# PCB_Draft_4.net
KiCad netlist of a schematic drawn in EAGLE
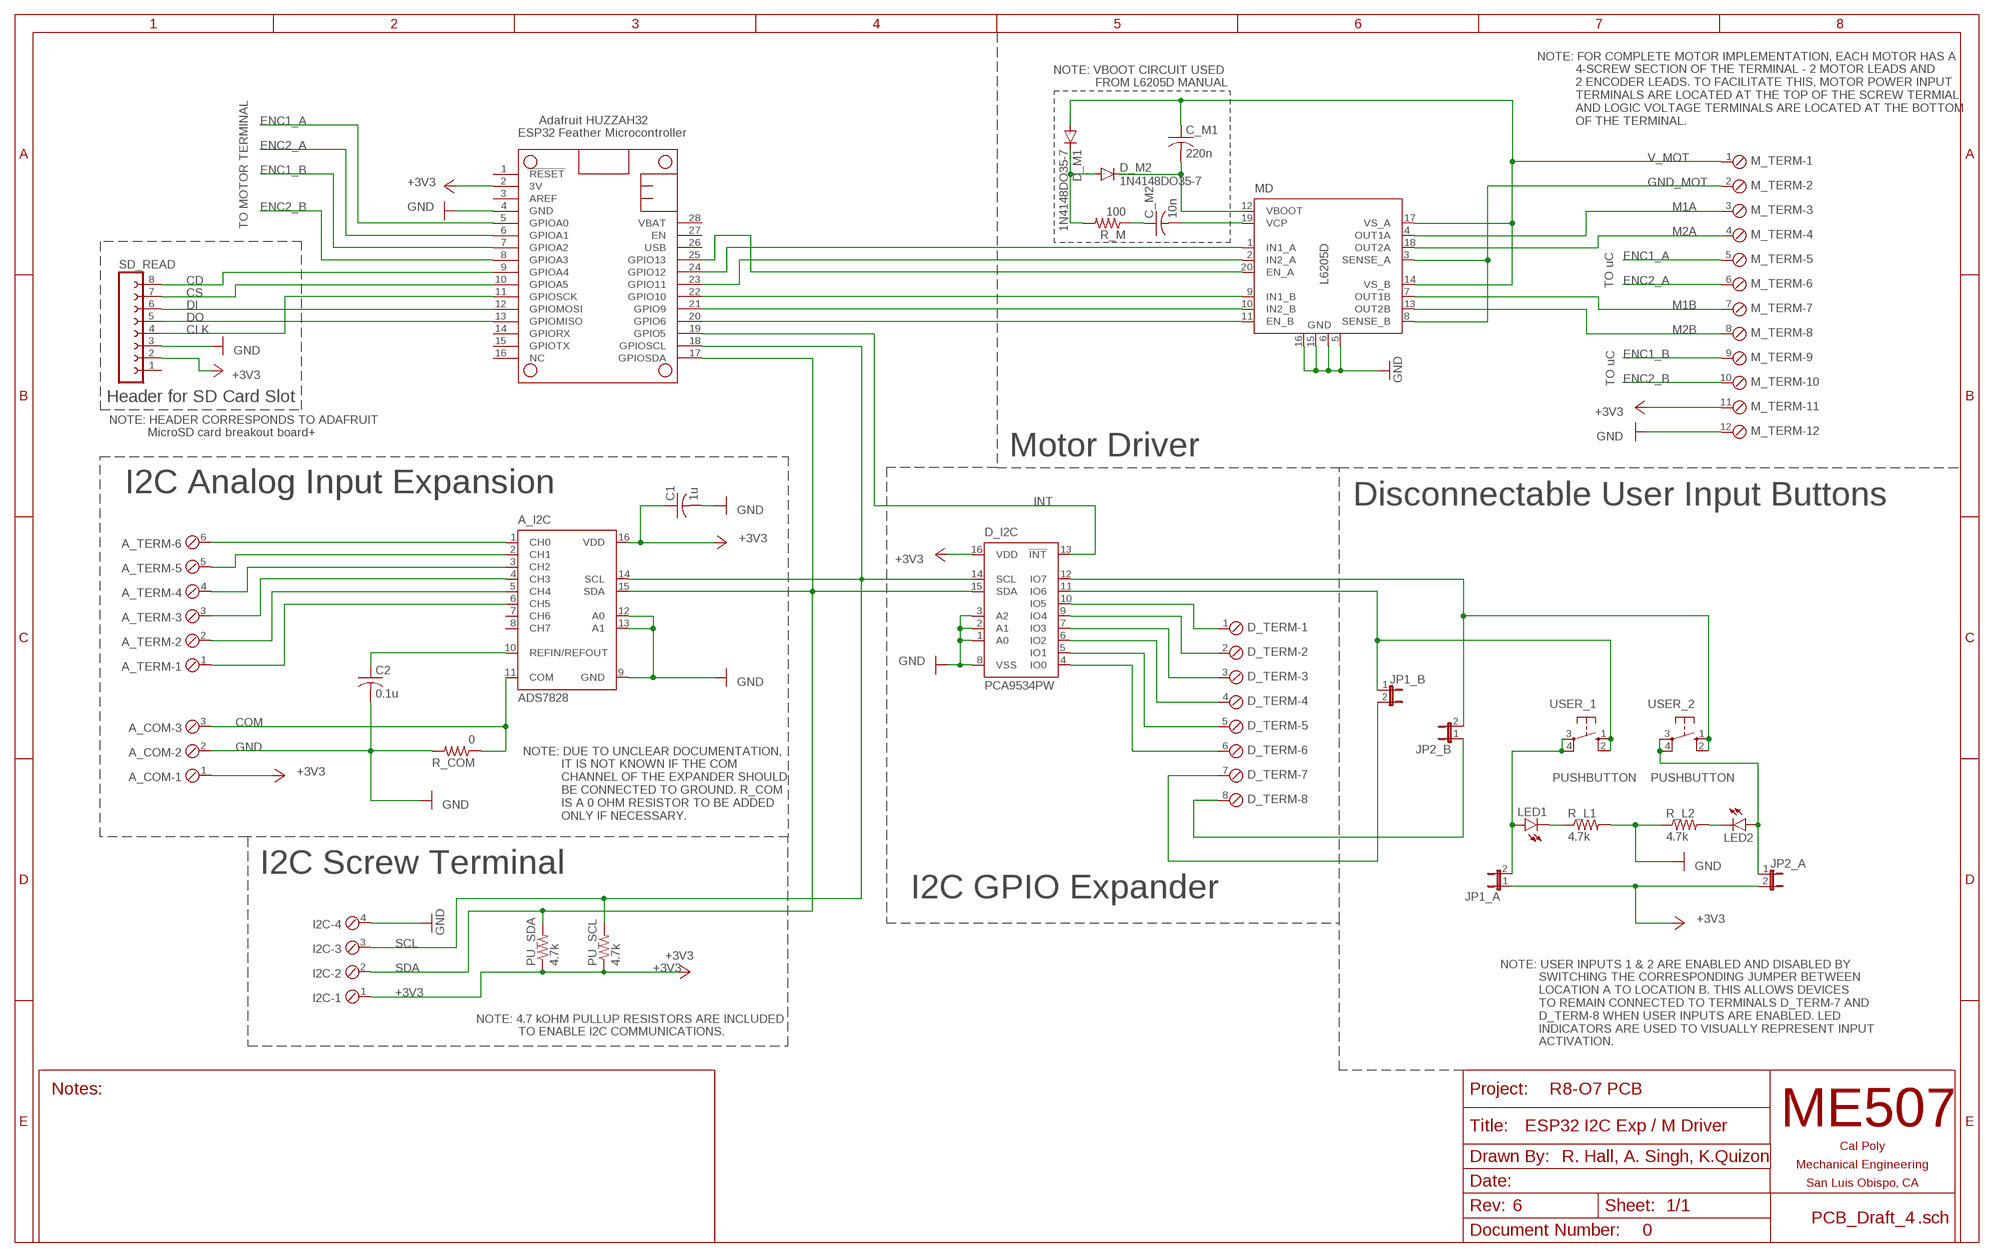
[diagram p0: schematic, sheet 1]

(export (version "E")
  (design (tool "Eeschema 10.0.6"))
  (components
    (comp (ref "A_COM")
      (value "SCREWTERM_3P_254")
      (footprint "eagle-import:3POL254")
      (libsource (lib "eagle-import") (part "SCREWTERM_3P_254"))
    )
    (comp (ref "A_I2C")
      (value "ADS7828")
      (footprint "eagle-import:TSSOP16-PW")
      (fields (field (name "MF") "TEXAS INSTRUMENTS") (field (name "MPN") "ADS7828E/250"))
      (libsource (lib "eagle-import") (part "ADS7828"))
    )
    (comp (ref "A_TERM")
      (value "SCREWTERM_6P_254")
      (footprint "eagle-import:6POL254")
      (libsource (lib "eagle-import") (part "SCREWTERM_6P_254"))
    )
    (comp (ref "C1")
      (value "1u")
      (footprint "eagle-import:C0805")
      (libsource (lib "eagle-import") (part "C-USC0805"))
    )
    (comp (ref "C2")
      (value "0.1u")
      (footprint "eagle-import:C0805")
      (libsource (lib "eagle-import") (part "C-USC0805"))
    )
    (comp (ref "C_M1")
      (value "220n")
      (footprint "eagle-import:C0805")
      (libsource (lib "eagle-import") (part "C-USC0805"))
    )
    (comp (ref "C_M2")
      (value "10n")
      (footprint "eagle-import:C0805")
      (libsource (lib "eagle-import") (part "C-USC0805"))
    )
    (comp (ref "D_I2C")
      (value "PCA9534PW")
      (footprint "eagle-import:TSSOP16")
      (libsource (lib "eagle-import") (part "PCA9534PW"))
    )
    (comp (ref "D_M1")
      (value "1N4148DO35-7")
      (footprint "eagle-import:DO35-7")
      (libsource (lib "eagle-import") (part "1N4148DO35-7"))
    )
    (comp (ref "D_M2")
      (value "1N4148DO35-7")
      (footprint "eagle-import:DO35-7")
      (libsource (lib "eagle-import") (part "1N4148DO35-7"))
    )
    (comp (ref "D_TERM")
      (value "SCREWTERM_8P_254")
      (footprint "eagle-import:8POL254")
      (libsource (lib "eagle-import") (part "SCREWTERM_8P_254"))
    )
    (comp (ref "FTHRWNG")
      (value "FEATHERWINGEXTENDED_BOTH_ENDS")
      (footprint "eagle-import:FEATHERWING")
      (libsource (lib "eagle-import") (part "FEATHERWINGEXTENDED_BOTH_ENDS"))
    )
    (comp (ref "I2C")
      (value "SCREWTERM_4P_254")
      (footprint "eagle-import:4POL254")
      (libsource (lib "eagle-import") (part "SCREWTERM_4P_254"))
    )
    (comp (ref "JP1_A")
      (value "JP1E")
      (footprint "eagle-import:JP1")
      (libsource (lib "eagle-import") (part "JP1E"))
    )
    (comp (ref "JP1_B")
      (value "JP1E")
      (footprint "eagle-import:JP1")
      (libsource (lib "eagle-import") (part "JP1E"))
    )
    (comp (ref "JP2_A")
      (value "JP1E")
      (footprint "eagle-import:JP1")
      (libsource (lib "eagle-import") (part "JP1E"))
    )
    (comp (ref "JP2_B")
      (value "JP1E")
      (footprint "eagle-import:JP1")
      (libsource (lib "eagle-import") (part "JP1E"))
    )
    (comp (ref "LED1")
      (value "LEDCHIP-LED0805")
      (footprint "eagle-import:CHIP-LED0805")
      (libsource (lib "eagle-import") (part "LEDCHIP-LED0805"))
    )
    (comp (ref "LED2")
      (value "LEDCHIP-LED0805")
      (footprint "eagle-import:CHIP-LED0805")
      (libsource (lib "eagle-import") (part "LEDCHIP-LED0805"))
    )
    (comp (ref "MD")
      (value "L6205D")
      (footprint "eagle-import:SO20")
      (libsource (lib "eagle-import") (part "L6205D"))
    )
    (comp (ref "M_TERM")
      (value "SCREWTERM_12P_254")
      (footprint "eagle-import:12POL254")
      (libsource (lib "eagle-import") (part "SCREWTERM_12P_254"))
    )
    (comp (ref "PU_SCL")
      (value "4.7k")
      (footprint "eagle-import:M0805")
      (libsource (lib "eagle-import") (part "R-US_M0805"))
    )
    (comp (ref "PU_SDA")
      (value "4.7k")
      (footprint "eagle-import:M0805")
      (libsource (lib "eagle-import") (part "R-US_M0805"))
    )
    (comp (ref "R_COM")
      (value "0")
      (footprint "eagle-import:M0805")
      (libsource (lib "eagle-import") (part "R-US_M0805"))
    )
    (comp (ref "R_L1")
      (value "4.7k")
      (footprint "eagle-import:M0805")
      (libsource (lib "eagle-import") (part "R-US_M0805"))
    )
    (comp (ref "R_L2")
      (value "4.7k")
      (footprint "eagle-import:M0805")
      (libsource (lib "eagle-import") (part "R-US_M0805"))
    )
    (comp (ref "R_M")
      (value "100")
      (footprint "eagle-import:M0805")
      (libsource (lib "eagle-import") (part "R-US_M0805"))
    )
    (comp (ref "SD_READ")
      (value "FE08-1")
      (footprint "eagle-import:FE08")
      (libsource (lib "eagle-import") (part "FE08-1"))
    )
    (comp (ref "USER_1")
      (value "PUSHBUTTON")
      (footprint "eagle-import:B3F-10XX")
      (fields (field (name "MPN") "B3F-1000"))
      (libsource (lib "eagle-import") (part "PUSHBUTTON"))
    )
    (comp (ref "USER_2")
      (value "PUSHBUTTON")
      (footprint "eagle-import:B3F-10XX")
      (fields (field (name "MPN") "B3F-1000"))
      (libsource (lib "eagle-import") (part "PUSHBUTTON"))
    )
  )
  (nets
    (net (code "1") (name "+3V3") (class "Default")
      (node (ref "A_COM") (pin "1") (pinfunction "1_1") (pintype "passive"))
      (node (ref "A_I2C") (pin "16") (pinfunction "VDD_16") (pintype "power_in"))
      (node (ref "C1") (pin "1") (pinfunction "1_1") (pintype "passive"))
      (node (ref "D_I2C") (pin "16") (pinfunction "VDD_16") (pintype "power_in"))
      (node (ref "FTHRWNG") (pin "2") (pinfunction "3V_2") (pintype "power_in"))
      (node (ref "I2C") (pin "1") (pinfunction "1_1") (pintype "passive"))
      (node (ref "JP1_A") (pin "1") (pinfunction "1_1") (pintype "passive"))
      (node (ref "JP2_A") (pin "2") (pinfunction "2_2") (pintype "passive"))
      (node (ref "M_TERM") (pin "11") (pinfunction "1_11") (pintype "passive"))
      (node (ref "PU_SCL") (pin "1") (pinfunction "1_1") (pintype "passive"))
      (node (ref "PU_SDA") (pin "1") (pinfunction "1_1") (pintype "passive"))
      (node (ref "SD_READ") (pin "2") (pinfunction "2_2") (pintype "passive"))
    )
    (net (code "2") (name "/CD") (class "Default")
      (node (ref "FTHRWNG") (pin "9") (pinfunction "GPIOA4_9") (pintype "bidirectional"))
      (node (ref "SD_READ") (pin "8") (pinfunction "8_8") (pintype "passive"))
    )
    (net (code "3") (name "/CLK") (class "Default")
      (node (ref "FTHRWNG") (pin "11") (pinfunction "GPIOSCK_11") (pintype "bidirectional"))
      (node (ref "SD_READ") (pin "4") (pinfunction "4_4") (pintype "passive"))
    )
    (net (code "4") (name "/COM") (class "Default")
      (node (ref "A_COM") (pin "3") (pinfunction "1_3") (pintype "passive"))
      (node (ref "A_I2C") (pin "11") (pinfunction "COM_11") (pintype "input"))
      (node (ref "R_COM") (pin "1") (pinfunction "1_1") (pintype "passive"))
    )
    (net (code "5") (name "/CS") (class "Default")
      (node (ref "FTHRWNG") (pin "10") (pinfunction "GPIOA5_10") (pintype "bidirectional"))
      (node (ref "SD_READ") (pin "7") (pinfunction "7_7") (pintype "passive"))
    )
    (net (code "6") (name "/DI") (class "Default")
      (node (ref "FTHRWNG") (pin "12") (pinfunction "GPIOMOSI_12") (pintype "bidirectional"))
      (node (ref "SD_READ") (pin "6") (pinfunction "6_6") (pintype "passive"))
    )
    (net (code "7") (name "/DO") (class "Default")
      (node (ref "FTHRWNG") (pin "13") (pinfunction "GPIOMISO_13") (pintype "bidirectional"))
      (node (ref "SD_READ") (pin "5") (pinfunction "5_5") (pintype "passive"))
    )
    (net (code "8") (name "/ENC1_A") (class "Default")
      (node (ref "FTHRWNG") (pin "5") (pinfunction "GPIOA0_5") (pintype "bidirectional"))
      (node (ref "M_TERM") (pin "5") (pinfunction "1_5") (pintype "passive"))
    )
    (net (code "9") (name "/ENC1_B") (class "Default")
      (node (ref "FTHRWNG") (pin "7") (pinfunction "GPIOA2_7") (pintype "bidirectional"))
      (node (ref "M_TERM") (pin "9") (pinfunction "1_9") (pintype "passive"))
    )
    (net (code "10") (name "/ENC2_A") (class "Default")
      (node (ref "FTHRWNG") (pin "6") (pinfunction "GPIOA1_6") (pintype "bidirectional"))
      (node (ref "M_TERM") (pin "6") (pinfunction "1_6") (pintype "passive"))
    )
    (net (code "11") (name "/ENC2_B") (class "Default")
      (node (ref "FTHRWNG") (pin "8") (pinfunction "GPIOA3_8") (pintype "bidirectional"))
      (node (ref "M_TERM") (pin "10") (pinfunction "1_10") (pintype "passive"))
    )
    (net (code "12") (name "/GND_MOT") (class "Default")
      (node (ref "MD") (pin "3") (pinfunction "SENSE_A_3") (pintype "input"))
      (node (ref "MD") (pin "8") (pinfunction "SENSE_B_8") (pintype "input"))
      (node (ref "M_TERM") (pin "2") (pinfunction "1_2") (pintype "passive"))
    )
    (net (code "13") (name "/INT") (class "Default")
      (node (ref "D_I2C") (pin "13") (pinfunction "~{INT}_13") (pintype "open_collector"))
      (node (ref "FTHRWNG") (pin "19") (pinfunction "GPIO5_19") (pintype "bidirectional"))
    )
    (net (code "14") (name "/M1A") (class "Default")
      (node (ref "MD") (pin "4") (pinfunction "OUT1A_4") (pintype "output"))
      (node (ref "M_TERM") (pin "3") (pinfunction "1_3") (pintype "passive"))
    )
    (net (code "15") (name "/M1B") (class "Default")
      (node (ref "MD") (pin "7") (pinfunction "OUT1B_7") (pintype "output"))
      (node (ref "M_TERM") (pin "7") (pinfunction "1_7") (pintype "passive"))
    )
    (net (code "16") (name "/M2A") (class "Default")
      (node (ref "MD") (pin "18") (pinfunction "OUT2A_18") (pintype "output"))
      (node (ref "M_TERM") (pin "4") (pinfunction "1_4") (pintype "passive"))
    )
    (net (code "17") (name "/M2B") (class "Default")
      (node (ref "MD") (pin "13") (pinfunction "OUT2B_13") (pintype "output"))
      (node (ref "M_TERM") (pin "8") (pinfunction "1_8") (pintype "passive"))
    )
    (net (code "18") (name "/SCL") (class "Default")
      (node (ref "A_I2C") (pin "14") (pinfunction "SCL_14") (pintype "input"))
      (node (ref "D_I2C") (pin "14") (pinfunction "SCL_14") (pintype "input"))
      (node (ref "FTHRWNG") (pin "18") (pinfunction "GPIOSCL_18") (pintype "bidirectional"))
      (node (ref "I2C") (pin "3") (pinfunction "1_3") (pintype "passive"))
      (node (ref "PU_SCL") (pin "2") (pinfunction "2_2") (pintype "passive"))
    )
    (net (code "19") (name "/SDA") (class "Default")
      (node (ref "A_I2C") (pin "15") (pinfunction "SDA_15") (pintype "bidirectional"))
      (node (ref "D_I2C") (pin "15") (pinfunction "SDA_15") (pintype "bidirectional"))
      (node (ref "FTHRWNG") (pin "17") (pinfunction "GPIOSDA_17") (pintype "bidirectional"))
      (node (ref "I2C") (pin "2") (pinfunction "1_2") (pintype "passive"))
      (node (ref "PU_SDA") (pin "2") (pinfunction "2_2") (pintype "passive"))
    )
    (net (code "20") (name "/USB") (class "Default")
      (node (ref "FTHRWNG") (pin "26") (pinfunction "USB_26") (pintype "power_in"))
    )
    (net (code "21") (name "/VBAT") (class "Default")
      (node (ref "FTHRWNG") (pin "28") (pinfunction "VBAT_28") (pintype "power_in"))
    )
    (net (code "22") (name "/V_MOT") (class "Default")
      (node (ref "C_M1") (pin "1") (pinfunction "1_1") (pintype "passive"))
      (node (ref "D_M1") (pin "A") (pinfunction "A_A") (pintype "passive"))
      (node (ref "MD") (pin "14") (pinfunction "VS_B_14") (pintype "power_in"))
      (node (ref "MD") (pin "17") (pinfunction "VS_A_17") (pintype "power_in"))
      (node (ref "M_TERM") (pin "1") (pinfunction "1_1") (pintype "passive"))
    )
    (net (code "23") (name "GND") (class "Default")
      (node (ref "A_COM") (pin "2") (pinfunction "1_2") (pintype "passive"))
      (node (ref "A_I2C") (pin "12") (pinfunction "A0_12") (pintype "input"))
      (node (ref "A_I2C") (pin "13") (pinfunction "A1_13") (pintype "input"))
      (node (ref "A_I2C") (pin "9") (pinfunction "GND_9") (pintype "power_in"))
      (node (ref "C1") (pin "2") (pinfunction "2_2") (pintype "passive"))
      (node (ref "C2") (pin "2") (pinfunction "2_2") (pintype "passive"))
      (node (ref "D_I2C") (pin "1") (pinfunction "A0_1") (pintype "input"))
      (node (ref "D_I2C") (pin "2") (pinfunction "A1_2") (pintype "input"))
      (node (ref "D_I2C") (pin "3") (pinfunction "A2_3") (pintype "input"))
      (node (ref "D_I2C") (pin "8") (pinfunction "VSS_8") (pintype "power_in"))
      (node (ref "FTHRWNG") (pin "4") (pinfunction "GND_4") (pintype "power_in"))
      (node (ref "I2C") (pin "4") (pinfunction "1_4") (pintype "passive"))
      (node (ref "MD") (pin "15") (pinfunction "GND_15") (pintype "power_in"))
      (node (ref "MD") (pin "16") (pinfunction "GND_16") (pintype "power_in"))
      (node (ref "MD") (pin "5") (pinfunction "GND_5") (pintype "power_in"))
      (node (ref "MD") (pin "6") (pinfunction "GND_6") (pintype "power_in"))
      (node (ref "M_TERM") (pin "12") (pinfunction "1_12") (pintype "passive"))
      (node (ref "R_COM") (pin "2") (pinfunction "2_2") (pintype "passive"))
      (node (ref "R_L1") (pin "2") (pinfunction "2_2") (pintype "passive"))
      (node (ref "R_L2") (pin "1") (pinfunction "1_1") (pintype "passive"))
      (node (ref "SD_READ") (pin "3") (pinfunction "3_3") (pintype "passive"))
    )
    (net (code "24") (name "Net-(A_I2C-CH0)") (class "Default")
      (node (ref "A_I2C") (pin "1") (pinfunction "CH0_1") (pintype "input"))
      (node (ref "A_TERM") (pin "6") (pinfunction "1_6") (pintype "passive"))
    )
    (net (code "25") (name "Net-(A_I2C-CH1)") (class "Default")
      (node (ref "A_I2C") (pin "2") (pinfunction "CH1_2") (pintype "input"))
      (node (ref "A_TERM") (pin "5") (pinfunction "1_5") (pintype "passive"))
    )
    (net (code "26") (name "Net-(A_I2C-CH2)") (class "Default")
      (node (ref "A_I2C") (pin "3") (pinfunction "CH2_3") (pintype "input"))
      (node (ref "A_TERM") (pin "4") (pinfunction "1_4") (pintype "passive"))
    )
    (net (code "27") (name "Net-(A_I2C-CH3)") (class "Default")
      (node (ref "A_I2C") (pin "4") (pinfunction "CH3_4") (pintype "input"))
      (node (ref "A_TERM") (pin "3") (pinfunction "1_3") (pintype "passive"))
    )
    (net (code "28") (name "Net-(A_I2C-CH4)") (class "Default")
      (node (ref "A_I2C") (pin "5") (pinfunction "CH4_5") (pintype "input"))
      (node (ref "A_TERM") (pin "2") (pinfunction "1_2") (pintype "passive"))
    )
    (net (code "29") (name "Net-(A_I2C-CH5)") (class "Default")
      (node (ref "A_I2C") (pin "6") (pinfunction "CH5_6") (pintype "input"))
      (node (ref "A_TERM") (pin "1") (pinfunction "1_1") (pintype "passive"))
    )
    (net (code "30") (name "Net-(A_I2C-REFIN{slash}REFOUT)") (class "Default")
      (node (ref "A_I2C") (pin "10") (pinfunction "REFIN/REFOUT_10") (pintype "passive"))
      (node (ref "C2") (pin "1") (pinfunction "1_1") (pintype "passive"))
    )
    (net (code "31") (name "Net-(C_M2-Pad1)") (class "Default")
      (node (ref "C_M2") (pin "1") (pinfunction "1_1") (pintype "passive"))
      (node (ref "R_M") (pin "1") (pinfunction "1_1") (pintype "passive"))
    )
    (net (code "32") (name "Net-(D_I2C-IO0)") (class "Default")
      (node (ref "D_I2C") (pin "4") (pinfunction "IO0_4") (pintype "bidirectional"))
      (node (ref "D_TERM") (pin "6") (pinfunction "1_6") (pintype "passive"))
    )
    (net (code "33") (name "Net-(D_I2C-IO1)") (class "Default")
      (node (ref "D_I2C") (pin "5") (pinfunction "IO1_5") (pintype "bidirectional"))
      (node (ref "D_TERM") (pin "5") (pinfunction "1_5") (pintype "passive"))
    )
    (net (code "34") (name "Net-(D_I2C-IO2)") (class "Default")
      (node (ref "D_I2C") (pin "6") (pinfunction "IO2_6") (pintype "bidirectional"))
      (node (ref "D_TERM") (pin "4") (pinfunction "1_4") (pintype "passive"))
    )
    (net (code "35") (name "Net-(D_I2C-IO3)") (class "Default")
      (node (ref "D_I2C") (pin "7") (pinfunction "IO3_7") (pintype "bidirectional"))
      (node (ref "D_TERM") (pin "3") (pinfunction "1_3") (pintype "passive"))
    )
    (net (code "36") (name "Net-(D_I2C-IO4)") (class "Default")
      (node (ref "D_I2C") (pin "9") (pinfunction "IO4_9") (pintype "bidirectional"))
      (node (ref "D_TERM") (pin "2") (pinfunction "1_2") (pintype "passive"))
    )
    (net (code "37") (name "Net-(D_I2C-IO5)") (class "Default")
      (node (ref "D_I2C") (pin "10") (pinfunction "IO5_10") (pintype "bidirectional"))
      (node (ref "D_TERM") (pin "1") (pinfunction "1_1") (pintype "passive"))
    )
    (net (code "38") (name "Net-(D_I2C-IO6)") (class "Default")
      (node (ref "D_I2C") (pin "11") (pinfunction "IO6_11") (pintype "bidirectional"))
      (node (ref "JP1_B") (pin "1") (pinfunction "1_1") (pintype "passive"))
      (node (ref "USER_1") (pin "1") (pinfunction "S_1") (pintype "passive"))
      (node (ref "USER_1") (pin "2") (pinfunction "S1_2") (pintype "passive"))
    )
    (net (code "39") (name "Net-(D_I2C-IO7)") (class "Default")
      (node (ref "D_I2C") (pin "12") (pinfunction "IO7_12") (pintype "bidirectional"))
      (node (ref "JP2_B") (pin "2") (pinfunction "2_2") (pintype "passive"))
      (node (ref "USER_2") (pin "1") (pinfunction "S_1") (pintype "passive"))
      (node (ref "USER_2") (pin "2") (pinfunction "S1_2") (pintype "passive"))
    )
    (net (code "40") (name "Net-(D_M1-PadC)") (class "Default")
      (node (ref "D_M1") (pin "C") (pinfunction "C_C") (pintype "passive"))
      (node (ref "D_M2") (pin "A") (pinfunction "A_A") (pintype "passive"))
      (node (ref "R_M") (pin "2") (pinfunction "2_2") (pintype "passive"))
    )
    (net (code "41") (name "Net-(D_TERMG-1)") (class "Default")
      (node (ref "D_TERM") (pin "7") (pinfunction "1_7") (pintype "passive"))
      (node (ref "JP1_B") (pin "2") (pinfunction "2_2") (pintype "passive"))
    )
    (net (code "42") (name "Net-(D_TERMH-1)") (class "Default")
      (node (ref "D_TERM") (pin "8") (pinfunction "1_8") (pintype "passive"))
      (node (ref "JP2_B") (pin "1") (pinfunction "1_1") (pintype "passive"))
    )
    (net (code "43") (name "Net-(FTHRWNG-GPIO6)") (class "Default")
      (node (ref "FTHRWNG") (pin "20") (pinfunction "GPIO6_20") (pintype "bidirectional"))
      (node (ref "MD") (pin "11") (pinfunction "EN_B_11") (pintype "input"))
    )
    (net (code "44") (name "Net-(FTHRWNG-GPIO9)") (class "Default")
      (node (ref "FTHRWNG") (pin "21") (pinfunction "GPIO9_21") (pintype "bidirectional"))
      (node (ref "MD") (pin "10") (pinfunction "IN2_B_10") (pintype "input"))
    )
    (net (code "45") (name "Net-(FTHRWNG-GPIO10)") (class "Default")
      (node (ref "FTHRWNG") (pin "22") (pinfunction "GPIO10_22") (pintype "bidirectional"))
      (node (ref "MD") (pin "9") (pinfunction "IN1_B_9") (pintype "input"))
    )
    (net (code "46") (name "Net-(FTHRWNG-GPIO11)") (class "Default")
      (node (ref "FTHRWNG") (pin "23") (pinfunction "GPIO11_23") (pintype "bidirectional"))
      (node (ref "MD") (pin "2") (pinfunction "IN2_A_2") (pintype "input"))
    )
    (net (code "47") (name "Net-(FTHRWNG-GPIO12)") (class "Default")
      (node (ref "FTHRWNG") (pin "24") (pinfunction "GPIO12_24") (pintype "bidirectional"))
      (node (ref "MD") (pin "1") (pinfunction "IN1_A_1") (pintype "input"))
    )
    (net (code "48") (name "Net-(FTHRWNG-GPIO13)") (class "Default")
      (node (ref "FTHRWNG") (pin "25") (pinfunction "GPIO13_25") (pintype "bidirectional"))
      (node (ref "MD") (pin "20") (pinfunction "EN_A_20") (pintype "input"))
    )
    (net (code "49") (name "Net-(LED1-PadC)") (class "Default")
      (node (ref "LED1") (pin "C") (pinfunction "C_C") (pintype "passive"))
      (node (ref "R_L1") (pin "1") (pinfunction "1_1") (pintype "passive"))
    )
    (net (code "50") (name "Net-(LED2-PadC)") (class "Default")
      (node (ref "LED2") (pin "C") (pinfunction "C_C") (pintype "passive"))
      (node (ref "R_L2") (pin "2") (pinfunction "2_2") (pintype "passive"))
    )
    (net (code "51") (name "Net-(MD-VBOOT)") (class "Default")
      (node (ref "C_M1") (pin "2") (pinfunction "2_2") (pintype "passive"))
      (node (ref "D_M2") (pin "C") (pinfunction "C_C") (pintype "passive"))
      (node (ref "MD") (pin "12") (pinfunction "VBOOT_12") (pintype "power_in"))
    )
    (net (code "52") (name "Net-(MD-VCP)") (class "Default")
      (node (ref "C_M2") (pin "2") (pinfunction "2_2") (pintype "passive"))
      (node (ref "MD") (pin "19") (pinfunction "VCP_19") (pintype "power_in"))
    )
    (net (code "53") (name "Net-(USER_1-P)") (class "Default")
      (node (ref "JP1_A") (pin "2") (pinfunction "2_2") (pintype "passive"))
      (node (ref "LED1") (pin "A") (pinfunction "A_A") (pintype "passive"))
      (node (ref "USER_1") (pin "3") (pinfunction "P_3") (pintype "passive"))
      (node (ref "USER_1") (pin "4") (pinfunction "P1_4") (pintype "passive"))
    )
    (net (code "54") (name "Net-(USER_2-P)") (class "Default")
      (node (ref "JP2_A") (pin "1") (pinfunction "1_1") (pintype "passive"))
      (node (ref "LED2") (pin "A") (pinfunction "A_A") (pintype "passive"))
      (node (ref "USER_2") (pin "3") (pinfunction "P_3") (pintype "passive"))
      (node (ref "USER_2") (pin "4") (pinfunction "P1_4") (pintype "passive"))
    )
    (net (code "55") (name "unconnected-(A_I2C-CH6-Pad7)") (class "Default")
      (node (ref "A_I2C") (pin "7") (pinfunction "CH6_7") (pintype "input"))
    )
    (net (code "56") (name "unconnected-(A_I2C-CH7-Pad8)") (class "Default")
      (node (ref "A_I2C") (pin "8") (pinfunction "CH7_8") (pintype "input"))
    )
    (net (code "57") (name "unconnected-(FTHRWNG-AREF-Pad3)") (class "Default")
      (node (ref "FTHRWNG") (pin "3") (pinfunction "AREF_3") (pintype "passive"))
    )
    (net (code "58") (name "unconnected-(FTHRWNG-EN-Pad27)") (class "Default")
      (node (ref "FTHRWNG") (pin "27") (pinfunction "EN_27") (pintype "passive"))
    )
    (net (code "59") (name "unconnected-(FTHRWNG-GPIORX-Pad14)") (class "Default")
      (node (ref "FTHRWNG") (pin "14") (pinfunction "GPIORX_14") (pintype "bidirectional"))
    )
    (net (code "60") (name "unconnected-(FTHRWNG-GPIOTX-Pad15)") (class "Default")
      (node (ref "FTHRWNG") (pin "15") (pinfunction "GPIOTX_15") (pintype "bidirectional"))
    )
    (net (code "61") (name "unconnected-(FTHRWNG-NC-Pad16)") (class "Default")
      (node (ref "FTHRWNG") (pin "16") (pinfunction "NC_16") (pintype "passive"))
    )
    (net (code "62") (name "unconnected-(FTHRWNG-~{RESET}-Pad1)") (class "Default")
      (node (ref "FTHRWNG") (pin "1") (pinfunction "~{RESET}_1") (pintype "input"))
    )
    (net (code "63") (name "unconnected-(SD_READ-Pad1)") (class "Default")
      (node (ref "SD_READ") (pin "1") (pinfunction "1_1") (pintype "passive"))
    )
  )
)
